# ReSpeaker_4-Mic_Array_for_Raspberry_Pi_v.net
KiCad netlist of a schematic drawn in EAGLE
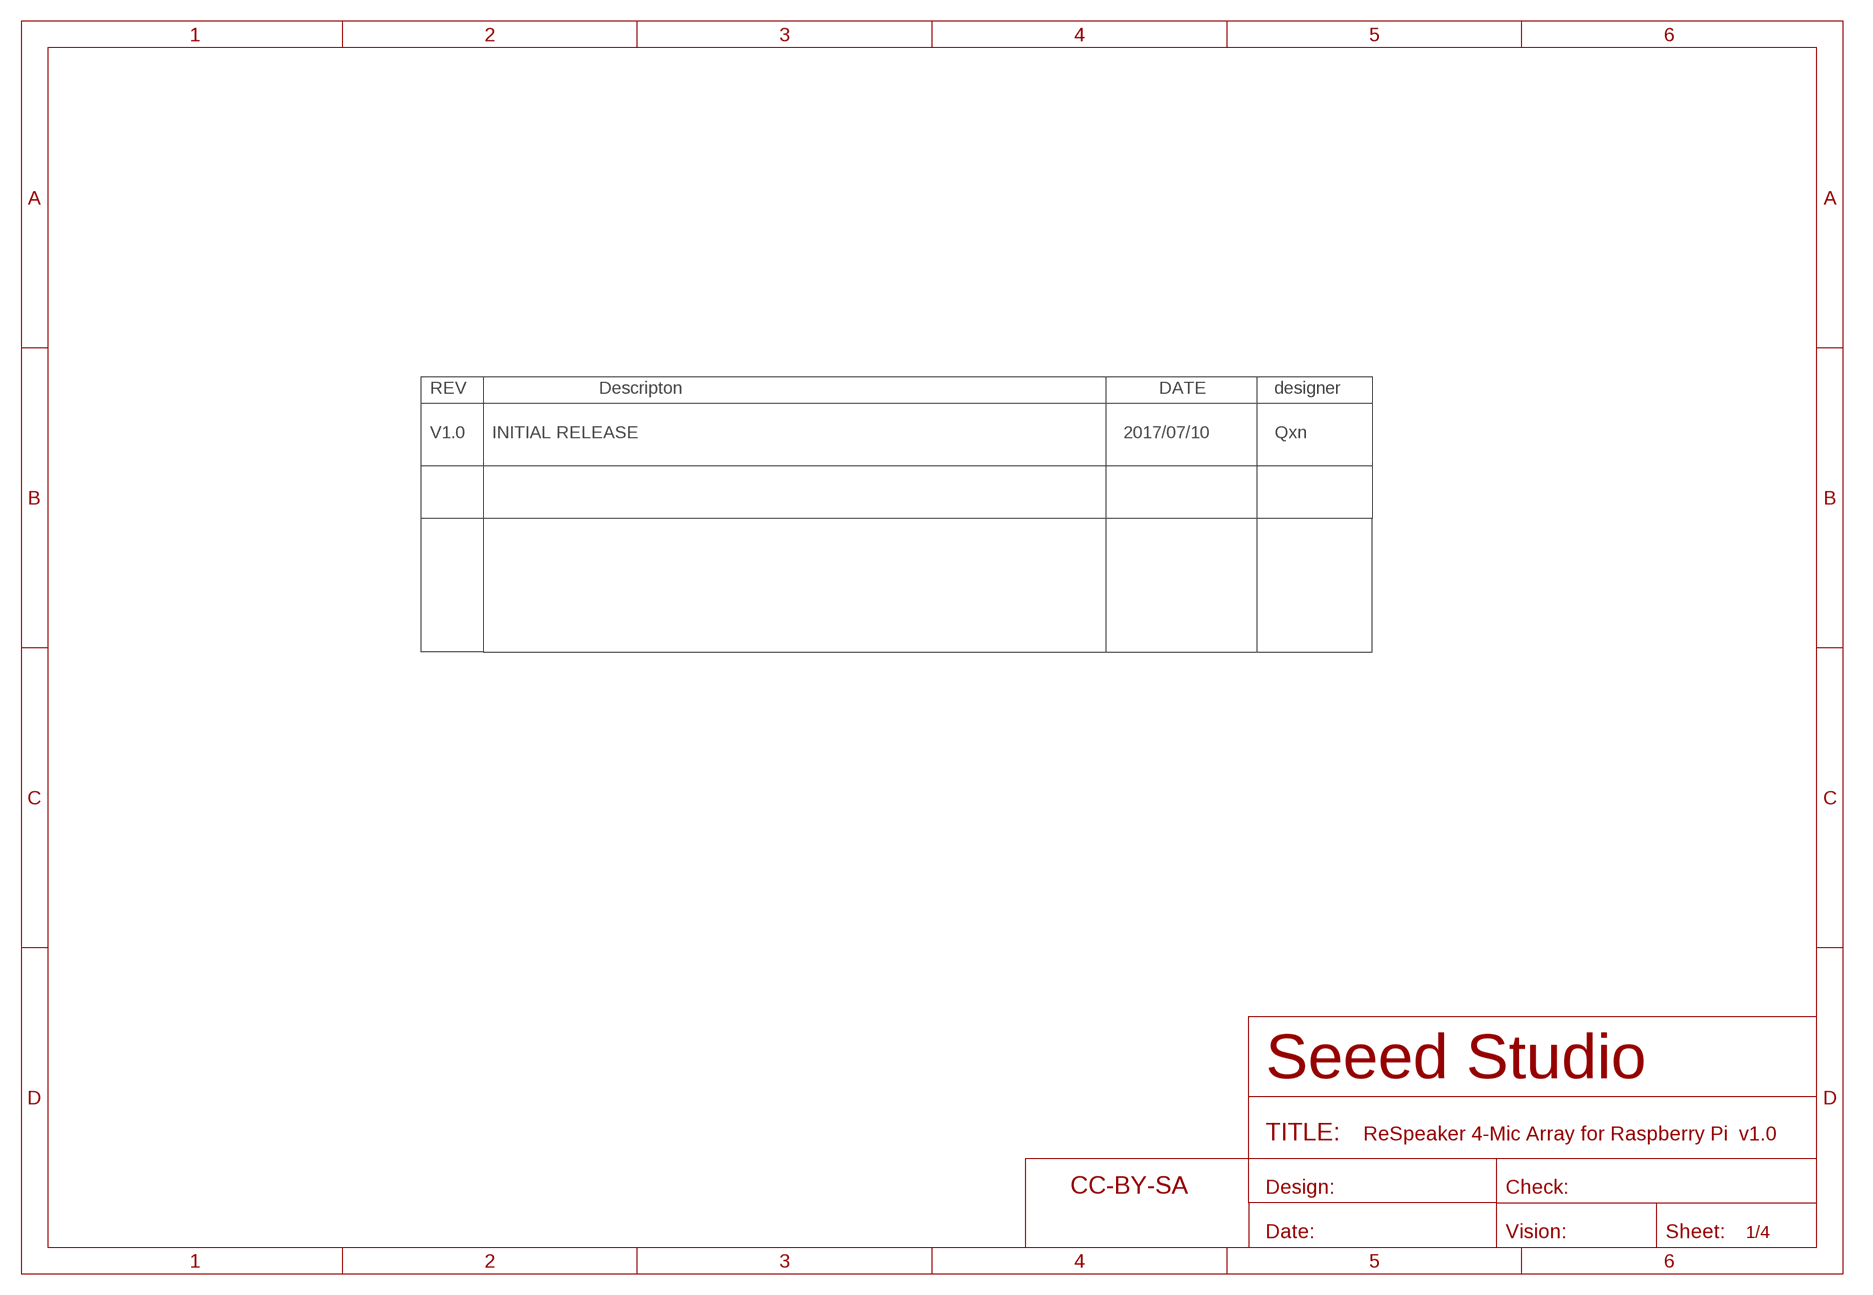
[diagram p0: schematic, sheet 1]
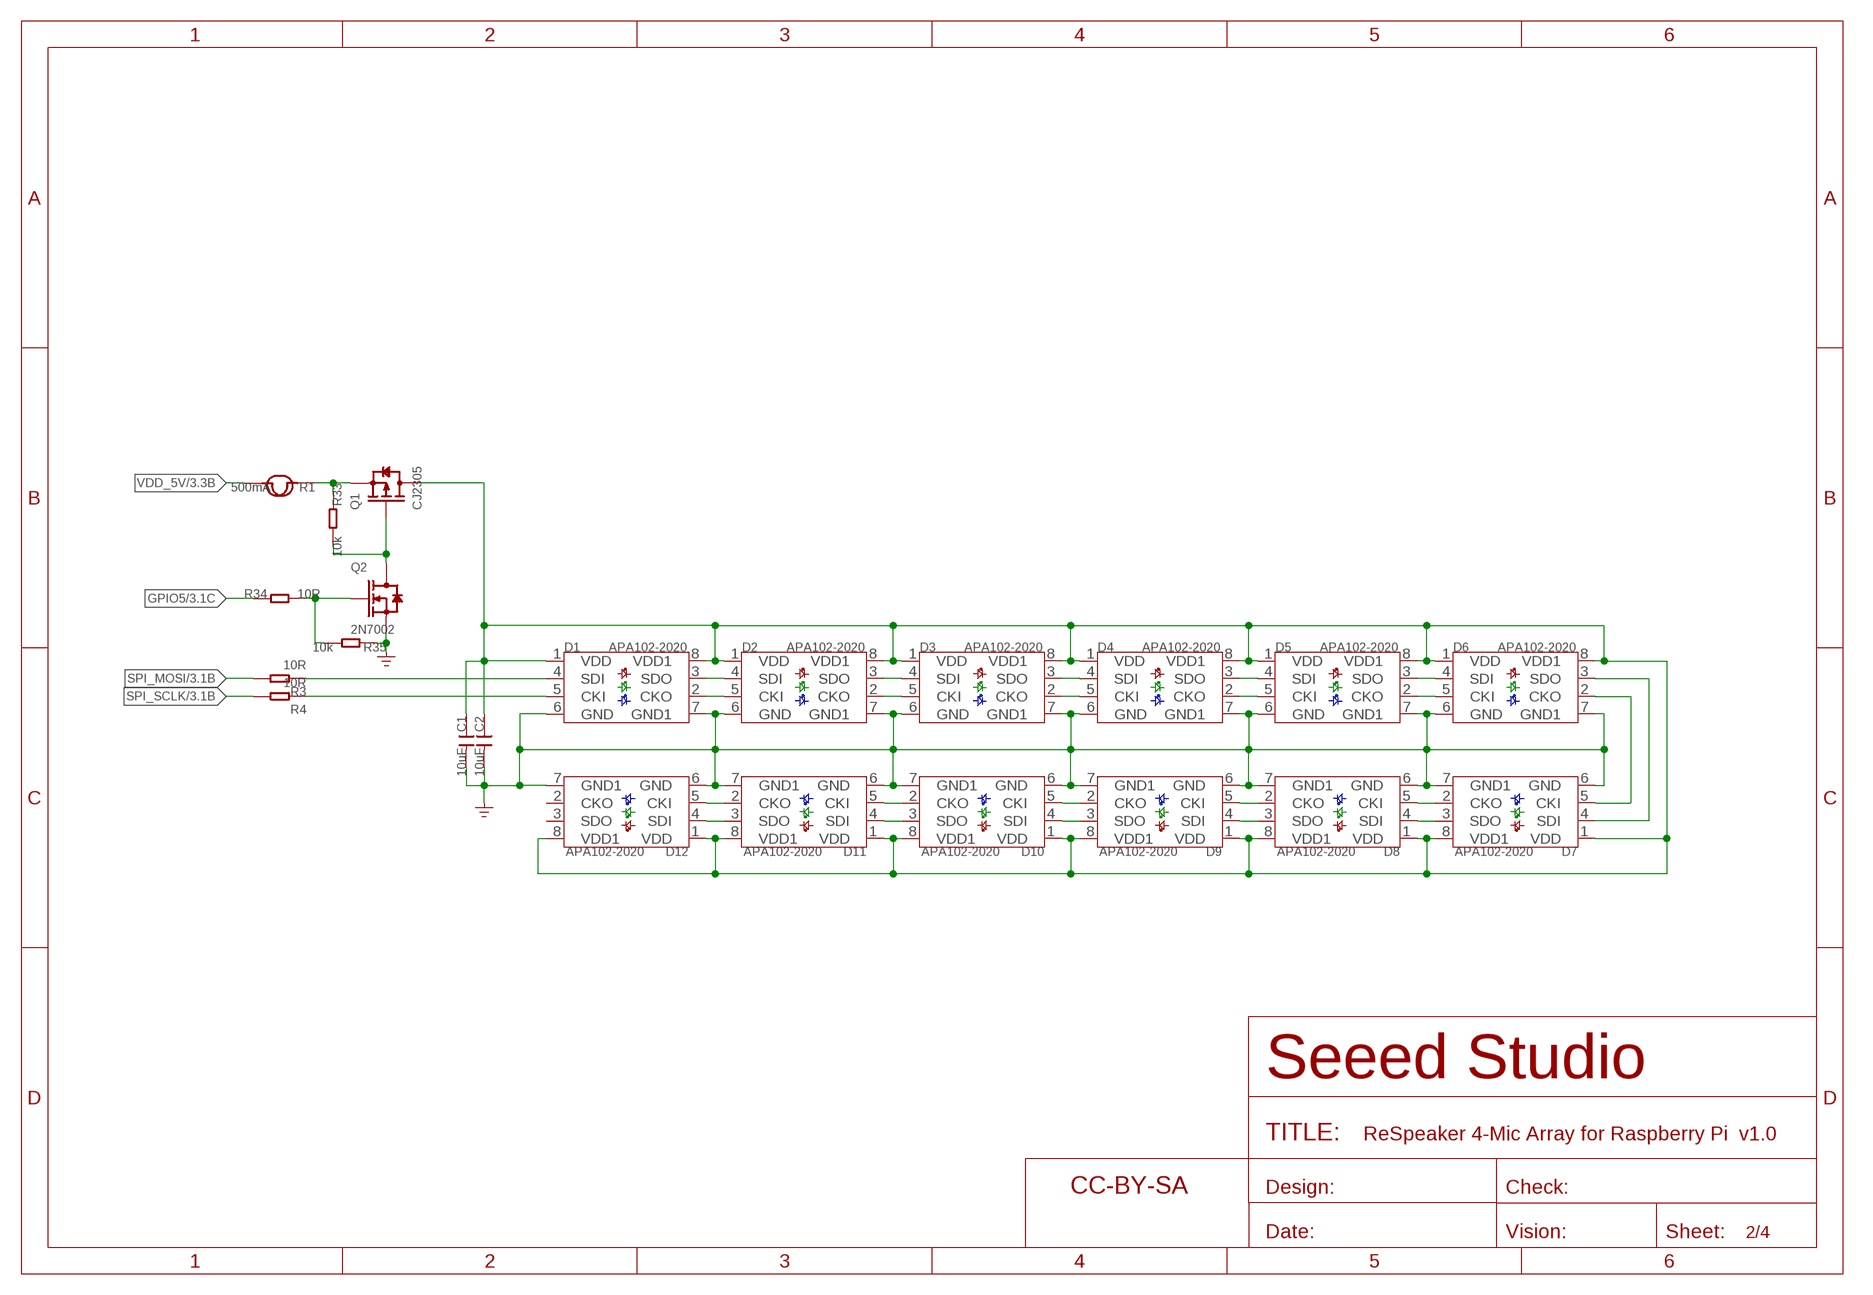
[diagram p1: schematic, sheet 2]
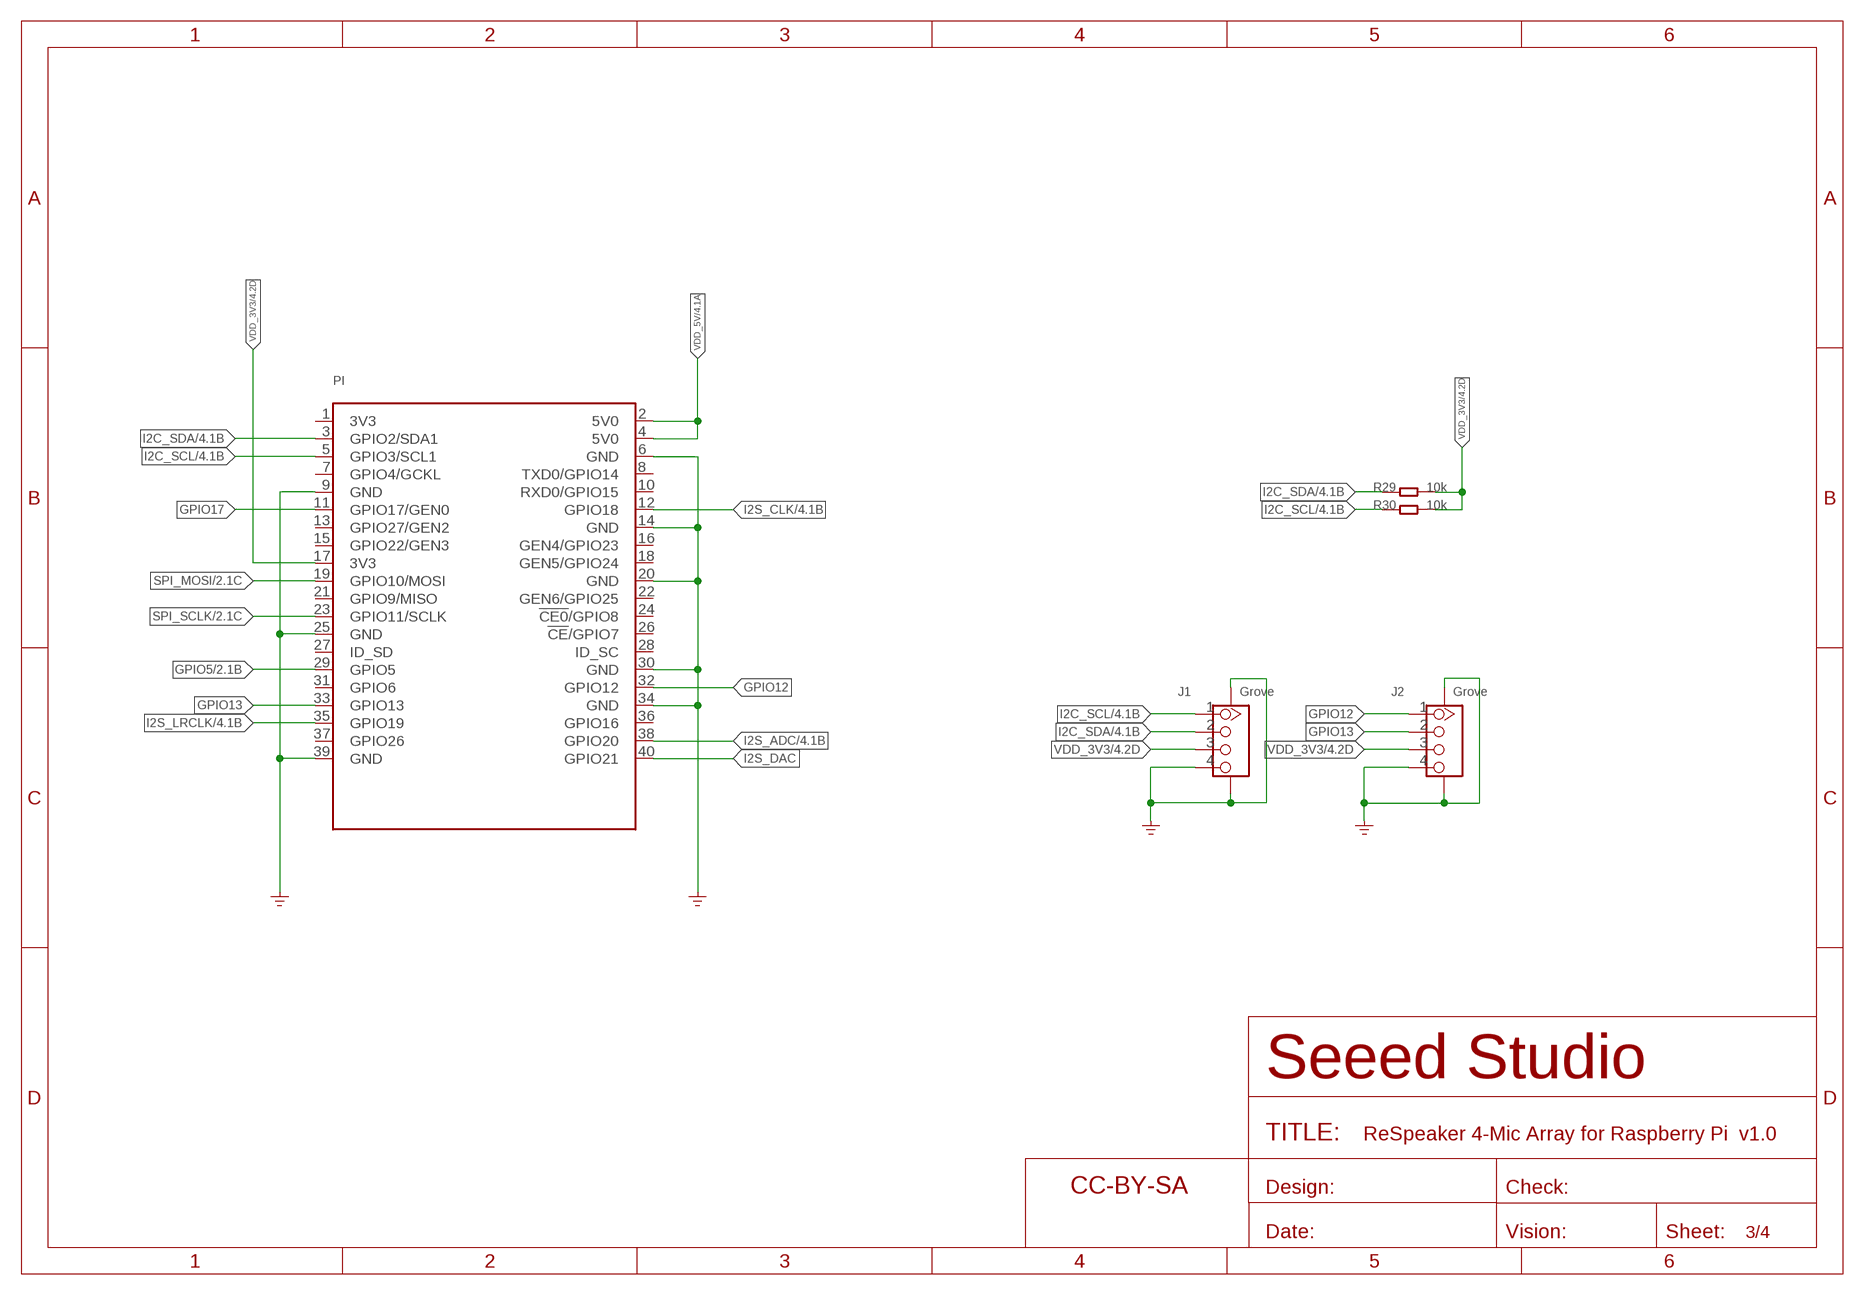
[diagram p2: schematic, sheet 3]
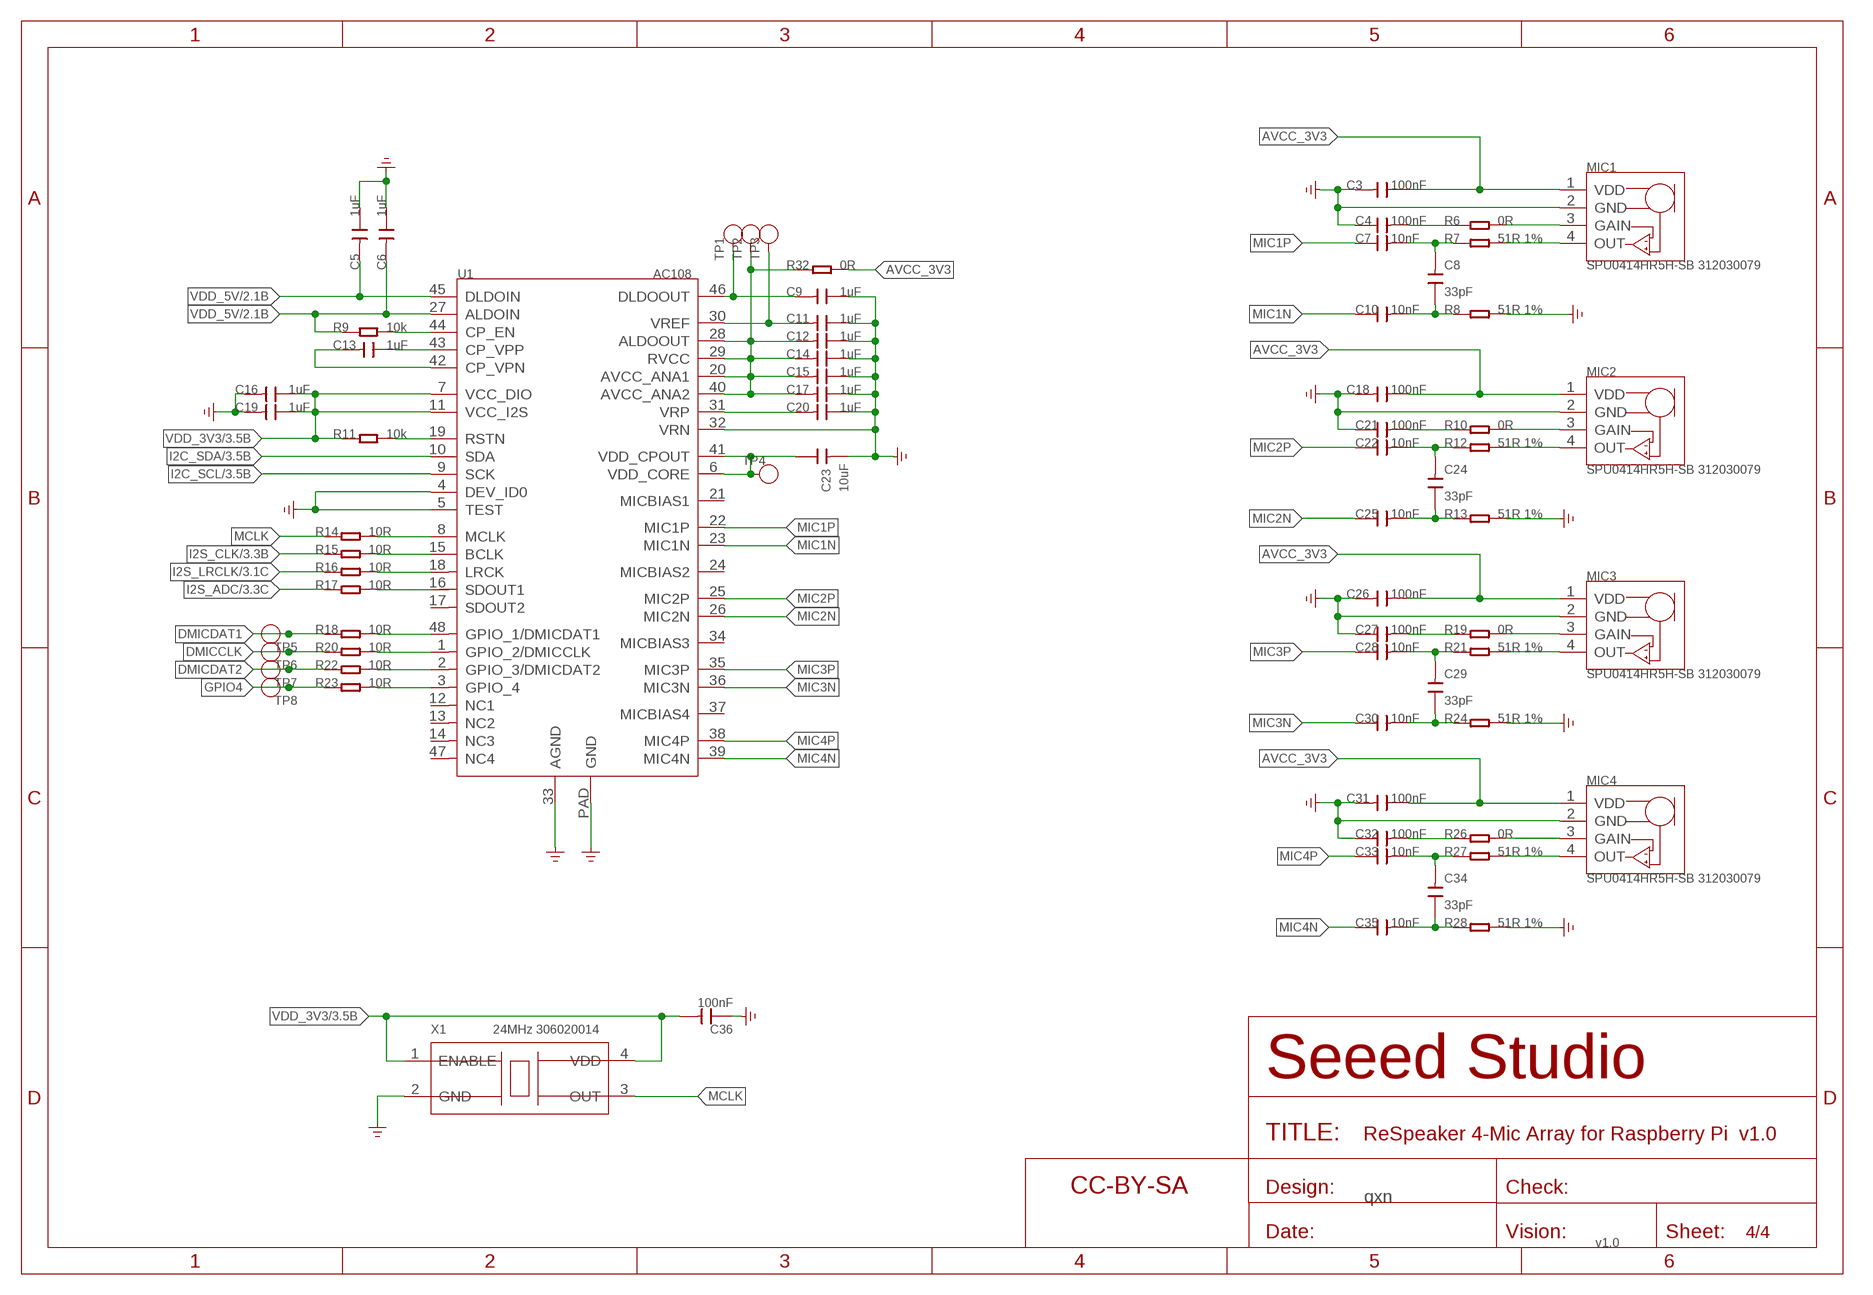
[diagram p3: schematic, sheet 4]

(export (version "E")
  (design (tool "Eeschema 10.0.6"))
  (components
    (comp (ref "FR1")
      (value "SEEEDSTUDIO-OPEN-SCH-FRAME")
      (footprint "eagle-import:SEEEDSTUDIO-PCB-FRAME")
      (libsource (lib "eagle-import") (part "SEEEDSTUDIO-OPEN-SCH-FRAME"))
    )
    (comp (ref "J1")
      (value "Grove")
      (footprint "eagle-import:HW4-SMD-2.0-90D")
      (libsource (lib "eagle-import") (part "GROVE-CONNECTOR-SMD'90D'"))
    )
    (comp (ref "J2")
      (value "Grove")
      (footprint "eagle-import:HW4-SMD-2.0-90D")
      (libsource (lib "eagle-import") (part "GROVE-CONNECTOR-SMD'90D'"))
    )
    (comp (ref "PI")
      (value "RPI-ZERO-BOTTOM")
      (footprint "eagle-import:H2X20-SMD-2.54")
      (libsource (lib "eagle-import") (part "RPI-ZERO-BOTTOM"))
    )
    (comp (ref "R29")
      (value "10k")
      (footprint "eagle-import:R0402")
      (libsource (lib "eagle-import") (part "RES-0402"))
    )
    (comp (ref "R30")
      (value "10k")
      (footprint "eagle-import:R0402")
      (libsource (lib "eagle-import") (part "RES-0402"))
    )
    (comp (ref "FR4")
      (value "SEEEDSTUDIO-OPEN-SCH-FRAME")
      (footprint "eagle-import:SEEEDSTUDIO-PCB-FRAME")
      (libsource (lib "eagle-import") (part "SEEEDSTUDIO-OPEN-SCH-FRAME"))
    )
    (comp (ref "C1")
      (value "10uF")
      (footprint "eagle-import:C0603")
      (libsource (lib "eagle-import") (part "CAP-0603"))
    )
    (comp (ref "C2")
      (value "10uF")
      (footprint "eagle-import:C0603")
      (libsource (lib "eagle-import") (part "CAP-0603"))
    )
    (comp (ref "D1")
      (value "APA102-2020")
      (footprint "eagle-import:RGB2020")
      (libsource (lib "eagle-import") (part "LED-RGB-8P-APA102-2020"))
    )
    (comp (ref "D2")
      (value "APA102-2020")
      (footprint "eagle-import:RGB2020")
      (libsource (lib "eagle-import") (part "LED-RGB-8P-APA102-2020"))
    )
    (comp (ref "D3")
      (value "APA102-2020")
      (footprint "eagle-import:RGB2020")
      (libsource (lib "eagle-import") (part "LED-RGB-8P-APA102-2020"))
    )
    (comp (ref "D4")
      (value "APA102-2020")
      (footprint "eagle-import:RGB2020")
      (libsource (lib "eagle-import") (part "LED-RGB-8P-APA102-2020"))
    )
    (comp (ref "D5")
      (value "APA102-2020")
      (footprint "eagle-import:RGB2020")
      (libsource (lib "eagle-import") (part "LED-RGB-8P-APA102-2020"))
    )
    (comp (ref "D6")
      (value "APA102-2020")
      (footprint "eagle-import:RGB2020")
      (libsource (lib "eagle-import") (part "LED-RGB-8P-APA102-2020"))
    )
    (comp (ref "D7")
      (value "APA102-2020")
      (footprint "eagle-import:RGB2020")
      (libsource (lib "eagle-import") (part "LED-RGB-8P-APA102-2020"))
    )
    (comp (ref "D8")
      (value "APA102-2020")
      (footprint "eagle-import:RGB2020")
      (libsource (lib "eagle-import") (part "LED-RGB-8P-APA102-2020"))
    )
    (comp (ref "D9")
      (value "APA102-2020")
      (footprint "eagle-import:RGB2020")
      (libsource (lib "eagle-import") (part "LED-RGB-8P-APA102-2020"))
    )
    (comp (ref "D10")
      (value "APA102-2020")
      (footprint "eagle-import:RGB2020")
      (libsource (lib "eagle-import") (part "LED-RGB-8P-APA102-2020"))
    )
    (comp (ref "D11")
      (value "APA102-2020")
      (footprint "eagle-import:RGB2020")
      (libsource (lib "eagle-import") (part "LED-RGB-8P-APA102-2020"))
    )
    (comp (ref "D12")
      (value "APA102-2020")
      (footprint "eagle-import:RGB2020")
      (libsource (lib "eagle-import") (part "LED-RGB-8P-APA102-2020"))
    )
    (comp (ref "FR3")
      (value "SEEEDSTUDIO-OPEN-SCH-FRAME")
      (footprint "eagle-import:SEEEDSTUDIO-PCB-FRAME")
      (libsource (lib "eagle-import") (part "SEEEDSTUDIO-OPEN-SCH-FRAME"))
    )
    (comp (ref "Q1")
      (value "CJ2305")
      (footprint "eagle-import:SOT-23")
      (libsource (lib "eagle-import") (part "MOSFET-P'SI2323CDS/SI2305DS{lt}BR{gt}'"))
    )
    (comp (ref "Q2")
      (value "2N7002")
      (footprint "eagle-import:SOT-23")
      (libsource (lib "eagle-import") (part "MOSFET-N'SOT23'"))
    )
    (comp (ref "R1")
      (value "500mA")
      (footprint "eagle-import:FS1206")
      (libsource (lib "eagle-import") (part "FUSE+'1206'"))
    )
    (comp (ref "R3")
      (value "10R")
      (footprint "eagle-import:R0402")
      (libsource (lib "eagle-import") (part "RES-0402"))
    )
    (comp (ref "R4")
      (value "10R")
      (footprint "eagle-import:R0402")
      (libsource (lib "eagle-import") (part "RES-0402"))
    )
    (comp (ref "R33")
      (value "10k")
      (footprint "eagle-import:R0402")
      (libsource (lib "eagle-import") (part "RES-0402"))
    )
    (comp (ref "R34")
      (value "10R")
      (footprint "eagle-import:R0402")
      (libsource (lib "eagle-import") (part "RES-0402"))
    )
    (comp (ref "R35")
      (value "10k")
      (footprint "eagle-import:R0402")
      (libsource (lib "eagle-import") (part "RES-0402"))
    )
    (comp (ref "C3")
      (value "100nF")
      (footprint "eagle-import:C0402")
      (libsource (lib "eagle-import") (part "CAP-0402"))
    )
    (comp (ref "C4")
      (value "100nF")
      (footprint "eagle-import:C0402")
      (libsource (lib "eagle-import") (part "CAP-0402"))
    )
    (comp (ref "C5")
      (value "1uF")
      (footprint "eagle-import:C0402")
      (libsource (lib "eagle-import") (part "CAP-0402"))
    )
    (comp (ref "C6")
      (value "1uF")
      (footprint "eagle-import:C0402")
      (libsource (lib "eagle-import") (part "CAP-0402"))
    )
    (comp (ref "C7")
      (value "10nF")
      (footprint "eagle-import:C0402")
      (libsource (lib "eagle-import") (part "CAP-0402"))
    )
    (comp (ref "C8")
      (value "33pF")
      (footprint "eagle-import:C0402")
      (libsource (lib "eagle-import") (part "CAP-0402"))
    )
    (comp (ref "C9")
      (value "1uF")
      (footprint "eagle-import:C0402")
      (libsource (lib "eagle-import") (part "CAP-0402"))
    )
    (comp (ref "C10")
      (value "10nF")
      (footprint "eagle-import:C0402")
      (libsource (lib "eagle-import") (part "CAP-0402"))
    )
    (comp (ref "C11")
      (value "1uF")
      (footprint "eagle-import:C0402")
      (libsource (lib "eagle-import") (part "CAP-0402"))
    )
    (comp (ref "C12")
      (value "1uF")
      (footprint "eagle-import:C0402")
      (libsource (lib "eagle-import") (part "CAP-0402"))
    )
    (comp (ref "C13")
      (value "1uF")
      (footprint "eagle-import:C0402")
      (libsource (lib "eagle-import") (part "CAP-0402"))
    )
    (comp (ref "C14")
      (value "1uF")
      (footprint "eagle-import:C0402")
      (libsource (lib "eagle-import") (part "CAP-0402"))
    )
    (comp (ref "C15")
      (value "1uF")
      (footprint "eagle-import:C0402")
      (libsource (lib "eagle-import") (part "CAP-0402"))
    )
    (comp (ref "C16")
      (value "1uF")
      (footprint "eagle-import:C0402")
      (libsource (lib "eagle-import") (part "CAP-0402"))
    )
    (comp (ref "C17")
      (value "1uF")
      (footprint "eagle-import:C0402")
      (libsource (lib "eagle-import") (part "CAP-0402"))
    )
    (comp (ref "C18")
      (value "100nF")
      (footprint "eagle-import:C0402")
      (libsource (lib "eagle-import") (part "CAP-0402"))
    )
    (comp (ref "C19")
      (value "1uF")
      (footprint "eagle-import:C0402")
      (libsource (lib "eagle-import") (part "CAP-0402"))
    )
    (comp (ref "C20")
      (value "1uF")
      (footprint "eagle-import:C0402")
      (libsource (lib "eagle-import") (part "CAP-0402"))
    )
    (comp (ref "C21")
      (value "100nF")
      (footprint "eagle-import:C0402")
      (libsource (lib "eagle-import") (part "CAP-0402"))
    )
    (comp (ref "C22")
      (value "10nF")
      (footprint "eagle-import:C0402")
      (libsource (lib "eagle-import") (part "CAP-0402"))
    )
    (comp (ref "C23")
      (value "10uF")
      (footprint "eagle-import:C0603")
      (libsource (lib "eagle-import") (part "CAP-0603"))
    )
    (comp (ref "C24")
      (value "33pF")
      (footprint "eagle-import:C0402")
      (libsource (lib "eagle-import") (part "CAP-0402"))
    )
    (comp (ref "C25")
      (value "10nF")
      (footprint "eagle-import:C0402")
      (libsource (lib "eagle-import") (part "CAP-0402"))
    )
    (comp (ref "C26")
      (value "100nF")
      (footprint "eagle-import:C0402")
      (libsource (lib "eagle-import") (part "CAP-0402"))
    )
    (comp (ref "C27")
      (value "100nF")
      (footprint "eagle-import:C0402")
      (libsource (lib "eagle-import") (part "CAP-0402"))
    )
    (comp (ref "C28")
      (value "10nF")
      (footprint "eagle-import:C0402")
      (libsource (lib "eagle-import") (part "CAP-0402"))
    )
    (comp (ref "C29")
      (value "33pF")
      (footprint "eagle-import:C0402")
      (libsource (lib "eagle-import") (part "CAP-0402"))
    )
    (comp (ref "C30")
      (value "10nF")
      (footprint "eagle-import:C0402")
      (libsource (lib "eagle-import") (part "CAP-0402"))
    )
    (comp (ref "C31")
      (value "100nF")
      (footprint "eagle-import:C0402")
      (libsource (lib "eagle-import") (part "CAP-0402"))
    )
    (comp (ref "C32")
      (value "100nF")
      (footprint "eagle-import:C0402")
      (libsource (lib "eagle-import") (part "CAP-0402"))
    )
    (comp (ref "C33")
      (value "10nF")
      (footprint "eagle-import:C0402")
      (libsource (lib "eagle-import") (part "CAP-0402"))
    )
    (comp (ref "C34")
      (value "33pF")
      (footprint "eagle-import:C0402")
      (libsource (lib "eagle-import") (part "CAP-0402"))
    )
    (comp (ref "C35")
      (value "10nF")
      (footprint "eagle-import:C0402")
      (libsource (lib "eagle-import") (part "CAP-0402"))
    )
    (comp (ref "C36")
      (value "100nF")
      (footprint "eagle-import:C0402")
      (libsource (lib "eagle-import") (part "CAP-0402"))
    )
    (comp (ref "FR2")
      (value "SEEEDSTUDIO-OPEN-SCH-FRAME")
      (footprint "eagle-import:SEEEDSTUDIO-PCB-FRAME")
      (libsource (lib "eagle-import") (part "SEEEDSTUDIO-OPEN-SCH-FRAME"))
    )
    (comp (ref "MIC1")
      (value "SPU0414HR5H-SB 312030079")
      (footprint "eagle-import:MIC4P-1.7-3.76X2.95X1.1MM")
      (libsource (lib "eagle-import") (part "MICROPHONE-SPU0414HR5H-SB"))
    )
    (comp (ref "MIC2")
      (value "SPU0414HR5H-SB 312030079")
      (footprint "eagle-import:MIC4P-1.7-3.76X2.95X1.1MM")
      (libsource (lib "eagle-import") (part "MICROPHONE-SPU0414HR5H-SB"))
    )
    (comp (ref "MIC3")
      (value "SPU0414HR5H-SB 312030079")
      (footprint "eagle-import:MIC4P-1.7-3.76X2.95X1.1MM")
      (libsource (lib "eagle-import") (part "MICROPHONE-SPU0414HR5H-SB"))
    )
    (comp (ref "MIC4")
      (value "SPU0414HR5H-SB 312030079")
      (footprint "eagle-import:MIC4P-1.7-3.76X2.95X1.1MM")
      (libsource (lib "eagle-import") (part "MICROPHONE-SPU0414HR5H-SB"))
    )
    (comp (ref "R6")
      (value "0R")
      (footprint "eagle-import:R0402")
      (libsource (lib "eagle-import") (part "RES-0402"))
    )
    (comp (ref "R7")
      (value "51R 1%")
      (footprint "eagle-import:R0402")
      (libsource (lib "eagle-import") (part "RES-0402"))
    )
    (comp (ref "R8")
      (value "51R 1%")
      (footprint "eagle-import:R0402")
      (libsource (lib "eagle-import") (part "RES-0402"))
    )
    (comp (ref "R9")
      (value "10k")
      (footprint "eagle-import:R0402")
      (libsource (lib "eagle-import") (part "RES-0402"))
    )
    (comp (ref "R10")
      (value "0R")
      (footprint "eagle-import:R0402")
      (libsource (lib "eagle-import") (part "RES-0402"))
    )
    (comp (ref "R11")
      (value "10k")
      (footprint "eagle-import:R0402")
      (libsource (lib "eagle-import") (part "RES-0402"))
    )
    (comp (ref "R12")
      (value "51R 1%")
      (footprint "eagle-import:R0402")
      (libsource (lib "eagle-import") (part "RES-0402"))
    )
    (comp (ref "R13")
      (value "51R 1%")
      (footprint "eagle-import:R0402")
      (libsource (lib "eagle-import") (part "RES-0402"))
    )
    (comp (ref "R14")
      (value "10R")
      (footprint "eagle-import:R0402")
      (libsource (lib "eagle-import") (part "RES-0402"))
    )
    (comp (ref "R15")
      (value "10R")
      (footprint "eagle-import:R0402")
      (libsource (lib "eagle-import") (part "RES-0402"))
    )
    (comp (ref "R16")
      (value "10R")
      (footprint "eagle-import:R0402")
      (libsource (lib "eagle-import") (part "RES-0402"))
    )
    (comp (ref "R17")
      (value "10R")
      (footprint "eagle-import:R0402")
      (libsource (lib "eagle-import") (part "RES-0402"))
    )
    (comp (ref "R18")
      (value "10R")
      (footprint "eagle-import:R0402")
      (libsource (lib "eagle-import") (part "RES-0402"))
    )
    (comp (ref "R19")
      (value "0R")
      (footprint "eagle-import:R0402")
      (libsource (lib "eagle-import") (part "RES-0402"))
    )
    (comp (ref "R20")
      (value "10R")
      (footprint "eagle-import:R0402")
      (libsource (lib "eagle-import") (part "RES-0402"))
    )
    (comp (ref "R21")
      (value "51R 1%")
      (footprint "eagle-import:R0402")
      (libsource (lib "eagle-import") (part "RES-0402"))
    )
    (comp (ref "R22")
      (value "10R")
      (footprint "eagle-import:R0402")
      (libsource (lib "eagle-import") (part "RES-0402"))
    )
    (comp (ref "R23")
      (value "10R")
      (footprint "eagle-import:R0402")
      (libsource (lib "eagle-import") (part "RES-0402"))
    )
    (comp (ref "R24")
      (value "51R 1%")
      (footprint "eagle-import:R0402")
      (libsource (lib "eagle-import") (part "RES-0402"))
    )
    (comp (ref "R26")
      (value "0R")
      (footprint "eagle-import:R0402")
      (libsource (lib "eagle-import") (part "RES-0402"))
    )
    (comp (ref "R27")
      (value "51R 1%")
      (footprint "eagle-import:R0402")
      (libsource (lib "eagle-import") (part "RES-0402"))
    )
    (comp (ref "R28")
      (value "51R 1%")
      (footprint "eagle-import:R0402")
      (libsource (lib "eagle-import") (part "RES-0402"))
    )
    (comp (ref "R32")
      (value "0R")
      (footprint "eagle-import:R0402")
      (libsource (lib "eagle-import") (part "RES-0402"))
    )
    (comp (ref "TP1")
      (value "TEST-POINT'4545'")
      (footprint "eagle-import:TP-D45MIL")
      (fields (field (name "PARTNO") "DNP"))
      (libsource (lib "eagle-import") (part "TEST-POINT'4545'"))
    )
    (comp (ref "TP2")
      (value "TEST-POINT'4545'")
      (footprint "eagle-import:TP-D45MIL")
      (fields (field (name "PARTNO") "DNP"))
      (libsource (lib "eagle-import") (part "TEST-POINT'4545'"))
    )
    (comp (ref "TP3")
      (value "TEST-POINT'4545'")
      (footprint "eagle-import:TP-D45MIL")
      (fields (field (name "PARTNO") "DNP"))
      (libsource (lib "eagle-import") (part "TEST-POINT'4545'"))
    )
    (comp (ref "TP4")
      (value "TEST-POINT'4545'")
      (footprint "eagle-import:TP-D45MIL")
      (fields (field (name "PARTNO") "DNP"))
      (libsource (lib "eagle-import") (part "TEST-POINT'4545'"))
    )
    (comp (ref "TP5")
      (value "TEST-POINT'4080'")
      (footprint "eagle-import:TP-80X40MIL")
      (libsource (lib "eagle-import") (part "TEST-POINT'4080'"))
    )
    (comp (ref "TP6")
      (value "TEST-POINT'4080'")
      (footprint "eagle-import:TP-80X40MIL")
      (libsource (lib "eagle-import") (part "TEST-POINT'4080'"))
    )
    (comp (ref "TP7")
      (value "TEST-POINT'4080'")
      (footprint "eagle-import:TP-80X40MIL")
      (libsource (lib "eagle-import") (part "TEST-POINT'4080'"))
    )
    (comp (ref "TP8")
      (value "TEST-POINT'4080'")
      (footprint "eagle-import:TP-80X40MIL")
      (libsource (lib "eagle-import") (part "TEST-POINT'4080'"))
    )
    (comp (ref "U1")
      (value "AC108")
      (footprint "eagle-import:QFN48G-0.4-6X6MM")
      (libsource (lib "eagle-import") (part "CONVERTER-ADC-AC108"))
    )
    (comp (ref "X1")
      (value "24MHz 306020014")
      (footprint "eagle-import:OSC4-SMD-2.5X2.0X0.8MM")
      (libsource (lib "eagle-import") (part "CRYSTAL-OSCILLATOR2.52.0"))
    )
  )
  (nets
    (net (code "1") (name "3V3") (class "Default")
      (node (ref "PI") (pin "1") (pinfunction "3V3_1") (pintype "power_in"))
    )
    (net (code "2") (name "AVCC_3V3") (class "Default")
      (node (ref "C18") (pin "1") (pinfunction "1_1") (pintype "passive"))
      (node (ref "C26") (pin "1") (pinfunction "1_1") (pintype "passive"))
      (node (ref "C3") (pin "1") (pinfunction "1_1") (pintype "passive"))
      (node (ref "C31") (pin "1") (pinfunction "1_1") (pintype "passive"))
      (node (ref "MIC1") (pin "1") (pinfunction "VDD_1") (pintype "bidirectional"))
      (node (ref "MIC2") (pin "1") (pinfunction "VDD_1") (pintype "bidirectional"))
      (node (ref "MIC3") (pin "1") (pinfunction "VDD_1") (pintype "bidirectional"))
      (node (ref "MIC4") (pin "1") (pinfunction "VDD_1") (pintype "bidirectional"))
      (node (ref "R32") (pin "1") (pinfunction "1_1") (pintype "passive"))
    )
    (net (code "3") (name "DMICCLK") (class "Default")
      (node (ref "R20") (pin "2") (pinfunction "2_2") (pintype "passive"))
      (node (ref "TP6") (pin "1") (pinfunction "T_1") (pintype "bidirectional"))
    )
    (net (code "4") (name "DMICDAT1") (class "Default")
      (node (ref "R18") (pin "2") (pinfunction "2_2") (pintype "passive"))
      (node (ref "TP5") (pin "1") (pinfunction "T_1") (pintype "bidirectional"))
    )
    (net (code "5") (name "DMICDAT2") (class "Default")
      (node (ref "R22") (pin "2") (pinfunction "2_2") (pintype "passive"))
      (node (ref "TP7") (pin "1") (pinfunction "T_1") (pintype "bidirectional"))
    )
    (net (code "6") (name "GND") (class "Default")
      (node (ref "C1") (pin "2") (pinfunction "2_2") (pintype "passive"))
      (node (ref "C11") (pin "1") (pinfunction "1_1") (pintype "passive"))
      (node (ref "C12") (pin "1") (pinfunction "1_1") (pintype "passive"))
      (node (ref "C14") (pin "1") (pinfunction "1_1") (pintype "passive"))
      (node (ref "C15") (pin "1") (pinfunction "1_1") (pintype "passive"))
      (node (ref "C16") (pin "2") (pinfunction "2_2") (pintype "passive"))
      (node (ref "C17") (pin "1") (pinfunction "1_1") (pintype "passive"))
      (node (ref "C18") (pin "2") (pinfunction "2_2") (pintype "passive"))
      (node (ref "C19") (pin "2") (pinfunction "2_2") (pintype "passive"))
      (node (ref "C2") (pin "2") (pinfunction "2_2") (pintype "passive"))
      (node (ref "C20") (pin "1") (pinfunction "1_1") (pintype "passive"))
      (node (ref "C21") (pin "1") (pinfunction "1_1") (pintype "passive"))
      (node (ref "C23") (pin "2") (pinfunction "2_2") (pintype "passive"))
      (node (ref "C26") (pin "2") (pinfunction "2_2") (pintype "passive"))
      (node (ref "C27") (pin "1") (pinfunction "1_1") (pintype "passive"))
      (node (ref "C3") (pin "2") (pinfunction "2_2") (pintype "passive"))
      (node (ref "C31") (pin "2") (pinfunction "2_2") (pintype "passive"))
      (node (ref "C32") (pin "1") (pinfunction "1_1") (pintype "passive"))
      (node (ref "C36") (pin "1") (pinfunction "1_1") (pintype "passive"))
      (node (ref "C4") (pin "1") (pinfunction "1_1") (pintype "passive"))
      (node (ref "C5") (pin "1") (pinfunction "1_1") (pintype "passive"))
      (node (ref "C6") (pin "1") (pinfunction "1_1") (pintype "passive"))
      (node (ref "C9") (pin "1") (pinfunction "1_1") (pintype "passive"))
      (node (ref "D1") (pin "6") (pinfunction "GND_6") (pintype "bidirectional"))
      (node (ref "D1") (pin "7") (pinfunction "GND1_7") (pintype "bidirectional"))
      (node (ref "D10") (pin "6") (pinfunction "GND_6") (pintype "bidirectional"))
      (node (ref "D10") (pin "7") (pinfunction "GND1_7") (pintype "bidirectional"))
      (node (ref "D11") (pin "6") (pinfunction "GND_6") (pintype "bidirectional"))
      (node (ref "D11") (pin "7") (pinfunction "GND1_7") (pintype "bidirectional"))
      (node (ref "D12") (pin "6") (pinfunction "GND_6") (pintype "bidirectional"))
      (node (ref "D12") (pin "7") (pinfunction "GND1_7") (pintype "bidirectional"))
      (node (ref "D2") (pin "6") (pinfunction "GND_6") (pintype "bidirectional"))
      (node (ref "D2") (pin "7") (pinfunction "GND1_7") (pintype "bidirectional"))
      (node (ref "D3") (pin "6") (pinfunction "GND_6") (pintype "bidirectional"))
      (node (ref "D3") (pin "7") (pinfunction "GND1_7") (pintype "bidirectional"))
      (node (ref "D4") (pin "6") (pinfunction "GND_6") (pintype "bidirectional"))
      (node (ref "D4") (pin "7") (pinfunction "GND1_7") (pintype "bidirectional"))
      (node (ref "D5") (pin "6") (pinfunction "GND_6") (pintype "bidirectional"))
      (node (ref "D5") (pin "7") (pinfunction "GND1_7") (pintype "bidirectional"))
      (node (ref "D6") (pin "6") (pinfunction "GND_6") (pintype "bidirectional"))
      (node (ref "D6") (pin "7") (pinfunction "GND1_7") (pintype "bidirectional"))
      (node (ref "D7") (pin "6") (pinfunction "GND_6") (pintype "bidirectional"))
      (node (ref "D7") (pin "7") (pinfunction "GND1_7") (pintype "bidirectional"))
      (node (ref "D8") (pin "6") (pinfunction "GND_6") (pintype "bidirectional"))
      (node (ref "D8") (pin "7") (pinfunction "GND1_7") (pintype "bidirectional"))
      (node (ref "D9") (pin "6") (pinfunction "GND_6") (pintype "bidirectional"))
      (node (ref "D9") (pin "7") (pinfunction "GND1_7") (pintype "bidirectional"))
      (node (ref "J1") (pin "4") (pinfunction "4_4") (pintype "bidirectional"))
      (node (ref "J1") (pin "SS1") (pinfunction "SS1_SS1") (pintype "bidirectional"))
      (node (ref "J1") (pin "SS2") (pinfunction "SS2_SS2") (pintype "bidirectional"))
      (node (ref "J2") (pin "4") (pinfunction "4_4") (pintype "bidirectional"))
      (node (ref "J2") (pin "SS1") (pinfunction "SS1_SS1") (pintype "bidirectional"))
      (node (ref "J2") (pin "SS2") (pinfunction "SS2_SS2") (pintype "bidirectional"))
      (node (ref "MIC1") (pin "2") (pinfunction "GND_2") (pintype "bidirectional"))
      (node (ref "MIC2") (pin "2") (pinfunction "GND_2") (pintype "bidirectional"))
      (node (ref "MIC3") (pin "2") (pinfunction "GND_2") (pintype "bidirectional"))
      (node (ref "MIC4") (pin "2") (pinfunction "GND_2") (pintype "bidirectional"))
      (node (ref "PI") (pin "14") (pinfunction "GND_14") (pintype "power_in"))
      (node (ref "PI") (pin "20") (pinfunction "GND_20") (pintype "power_in"))
      (node (ref "PI") (pin "25") (pinfunction "GND_25") (pintype "power_in"))
      (node (ref "PI") (pin "30") (pinfunction "GND_30") (pintype "power_in"))
      (node (ref "PI") (pin "34") (pinfunction "GND_34") (pintype "power_in"))
      (node (ref "PI") (pin "39") (pinfunction "GND_39") (pintype "power_in"))
      (node (ref "PI") (pin "6") (pinfunction "GND_6") (pintype "power_in"))
      (node (ref "PI") (pin "9") (pinfunction "GND_9") (pintype "power_in"))
      (node (ref "Q2") (pin "2") (pinfunction "S_2") (pintype "passive"))
      (node (ref "R13") (pin "1") (pinfunction "1_1") (pintype "passive"))
      (node (ref "R24") (pin "1") (pinfunction "1_1") (pintype "passive"))
      (node (ref "R28") (pin "1") (pinfunction "1_1") (pintype "passive"))
      (node (ref "R35") (pin "1") (pinfunction "1_1") (pintype "passive"))
      (node (ref "R8") (pin "1") (pinfunction "1_1") (pintype "passive"))
      (node (ref "U1") (pin "32") (pinfunction "VRN_32") (pintype "bidirectional"))
      (node (ref "U1") (pin "33") (pinfunction "AGND_33") (pintype "bidirectional"))
      (node (ref "U1") (pin "4") (pinfunction "DEV_ID0_4") (pintype "bidirectional"))
      (node (ref "U1") (pin "5") (pinfunction "TEST_5") (pintype "bidirectional"))
      (node (ref "U1") (pin "PAD") (pinfunction "GND_PAD") (pintype "bidirectional"))
      (node (ref "X1") (pin "2") (pinfunction "GND_2") (pintype "bidirectional"))
    )
    (net (code "7") (name "GPIO4") (class "Default")
      (node (ref "R23") (pin "2") (pinfunction "2_2") (pintype "passive"))
      (node (ref "TP8") (pin "1") (pinfunction "T_1") (pintype "bidirectional"))
    )
    (net (code "8") (name "GPIO5") (class "Default")
      (node (ref "PI") (pin "29") (pinfunction "GPIO5_29") (pintype "bidirectional"))
      (node (ref "R34") (pin "1") (pinfunction "1_1") (pintype "passive"))
    )
    (net (code "9") (name "GPIO12") (class "Default")
      (node (ref "J2") (pin "1") (pinfunction "1_1") (pintype "bidirectional"))
      (node (ref "PI") (pin "32") (pinfunction "GPIO12_32") (pintype "bidirectional"))
    )
    (net (code "10") (name "GPIO13") (class "Default")
      (node (ref "J2") (pin "2") (pinfunction "2_2") (pintype "bidirectional"))
      (node (ref "PI") (pin "33") (pinfunction "GPIO13_33") (pintype "bidirectional"))
    )
    (net (code "11") (name "GPIO17") (class "Default")
      (node (ref "PI") (pin "11") (pinfunction "GPIO17/GEN0_11") (pintype "bidirectional"))
    )
    (net (code "12") (name "I2C_SCL") (class "Default")
      (node (ref "J1") (pin "1") (pinfunction "1_1") (pintype "bidirectional"))
      (node (ref "PI") (pin "5") (pinfunction "GPIO3/SCL1_5") (pintype "bidirectional"))
      (node (ref "R30") (pin "1") (pinfunction "1_1") (pintype "passive"))
      (node (ref "U1") (pin "9") (pinfunction "SCK_9") (pintype "bidirectional"))
    )
    (net (code "13") (name "I2C_SDA") (class "Default")
      (node (ref "J1") (pin "2") (pinfunction "2_2") (pintype "bidirectional"))
      (node (ref "PI") (pin "3") (pinfunction "GPIO2/SDA1_3") (pintype "bidirectional"))
      (node (ref "R29") (pin "1") (pinfunction "1_1") (pintype "passive"))
      (node (ref "U1") (pin "10") (pinfunction "SDA_10") (pintype "bidirectional"))
    )
    (net (code "14") (name "I2S_ADC") (class "Default")
      (node (ref "PI") (pin "38") (pinfunction "GPIO20_38") (pintype "bidirectional"))
      (node (ref "R17") (pin "2") (pinfunction "2_2") (pintype "passive"))
    )
    (net (code "15") (name "I2S_CLK") (class "Default")
      (node (ref "PI") (pin "12") (pinfunction "GPIO18_12") (pintype "bidirectional"))
      (node (ref "R15") (pin "2") (pinfunction "2_2") (pintype "passive"))
    )
    (net (code "16") (name "I2S_DAC") (class "Default")
      (node (ref "PI") (pin "40") (pinfunction "GPIO21_40") (pintype "bidirectional"))
    )
    (net (code "17") (name "I2S_LRCLK") (class "Default")
      (node (ref "PI") (pin "35") (pinfunction "GPIO19_35") (pintype "bidirectional"))
      (node (ref "R16") (pin "2") (pinfunction "2_2") (pintype "passive"))
    )
    (net (code "18") (name "MCLK") (class "Default")
      (node (ref "R14") (pin "2") (pinfunction "2_2") (pintype "passive"))
      (node (ref "X1") (pin "3") (pinfunction "OUT_3") (pintype "bidirectional"))
    )
    (net (code "19") (name "MIC1N") (class "Default")
      (node (ref "C10") (pin "1") (pinfunction "1_1") (pintype "passive"))
      (node (ref "U1") (pin "23") (pinfunction "MIC1N_23") (pintype "bidirectional"))
    )
    (net (code "20") (name "MIC1P") (class "Default")
      (node (ref "C7") (pin "1") (pinfunction "1_1") (pintype "passive"))
      (node (ref "U1") (pin "22") (pinfunction "MIC1P_22") (pintype "bidirectional"))
    )
    (net (code "21") (name "MIC2N") (class "Default")
      (node (ref "C25") (pin "1") (pinfunction "1_1") (pintype "passive"))
      (node (ref "U1") (pin "26") (pinfunction "MIC2N_26") (pintype "bidirectional"))
    )
    (net (code "22") (name "MIC2P") (class "Default")
      (node (ref "C22") (pin "1") (pinfunction "1_1") (pintype "passive"))
      (node (ref "U1") (pin "25") (pinfunction "MIC2P_25") (pintype "bidirectional"))
    )
    (net (code "23") (name "MIC3N") (class "Default")
      (node (ref "C30") (pin "1") (pinfunction "1_1") (pintype "passive"))
      (node (ref "U1") (pin "36") (pinfunction "MIC3N_36") (pintype "bidirectional"))
    )
    (net (code "24") (name "MIC3P") (class "Default")
      (node (ref "C28") (pin "1") (pinfunction "1_1") (pintype "passive"))
      (node (ref "U1") (pin "35") (pinfunction "MIC3P_35") (pintype "bidirectional"))
    )
    (net (code "25") (name "MIC4N") (class "Default")
      (node (ref "C35") (pin "1") (pinfunction "1_1") (pintype "passive"))
      (node (ref "U1") (pin "39") (pinfunction "MIC4N_39") (pintype "bidirectional"))
    )
    (net (code "26") (name "MIC4P") (class "Default")
      (node (ref "C33") (pin "1") (pinfunction "1_1") (pintype "passive"))
      (node (ref "U1") (pin "38") (pinfunction "MIC4P_38") (pintype "bidirectional"))
    )
    (net (code "27") (name "Net-(C4-Pad2)") (class "Default")
      (node (ref "C4") (pin "2") (pinfunction "2_2") (pintype "passive"))
      (node (ref "R6") (pin "2") (pinfunction "2_2") (pintype "passive"))
    )
    (net (code "28") (name "Net-(C7-Pad2)") (class "Default")
      (node (ref "C7") (pin "2") (pinfunction "2_2") (pintype "passive"))
      (node (ref "C8") (pin "2") (pinfunction "2_2") (pintype "passive"))
      (node (ref "R7") (pin "2") (pinfunction "2_2") (pintype "passive"))
    )
    (net (code "29") (name "Net-(C10-Pad2)") (class "Default")
      (node (ref "C10") (pin "2") (pinfunction "2_2") (pintype "passive"))
      (node (ref "C8") (pin "1") (pinfunction "1_1") (pintype "passive"))
      (node (ref "R8") (pin "2") (pinfunction "2_2") (pintype "passive"))
    )
    (net (code "30") (name "Net-(C21-Pad2)") (class "Default")
      (node (ref "C21") (pin "2") (pinfunction "2_2") (pintype "passive"))
      (node (ref "R10") (pin "2") (pinfunction "2_2") (pintype "passive"))
    )
    (net (code "31") (name "Net-(C22-Pad2)") (class "Default")
      (node (ref "C22") (pin "2") (pinfunction "2_2") (pintype "passive"))
      (node (ref "C24") (pin "2") (pinfunction "2_2") (pintype "passive"))
      (node (ref "R12") (pin "2") (pinfunction "2_2") (pintype "passive"))
    )
    (net (code "32") (name "Net-(C24-Pad1)") (class "Default")
      (node (ref "C24") (pin "1") (pinfunction "1_1") (pintype "passive"))
      (node (ref "C25") (pin "2") (pinfunction "2_2") (pintype "passive"))
      (node (ref "R13") (pin "2") (pinfunction "2_2") (pintype "passive"))
    )
    (net (code "33") (name "Net-(C27-Pad2)") (class "Default")
      (node (ref "C27") (pin "2") (pinfunction "2_2") (pintype "passive"))
      (node (ref "R19") (pin "2") (pinfunction "2_2") (pintype "passive"))
    )
    (net (code "34") (name "Net-(C28-Pad2)") (class "Default")
      (node (ref "C28") (pin "2") (pinfunction "2_2") (pintype "passive"))
      (node (ref "C29") (pin "2") (pinfunction "2_2") (pintype "passive"))
      (node (ref "R21") (pin "2") (pinfunction "2_2") (pintype "passive"))
    )
    (net (code "35") (name "Net-(C29-Pad1)") (class "Default")
      (node (ref "C29") (pin "1") (pinfunction "1_1") (pintype "passive"))
      (node (ref "C30") (pin "2") (pinfunction "2_2") (pintype "passive"))
      (node (ref "R24") (pin "2") (pinfunction "2_2") (pintype "passive"))
    )
    (net (code "36") (name "Net-(C32-Pad2)") (class "Default")
      (node (ref "C32") (pin "2") (pinfunction "2_2") (pintype "passive"))
      (node (ref "R26") (pin "2") (pinfunction "2_2") (pintype "passive"))
    )
    (net (code "37") (name "Net-(C33-Pad2)") (class "Default")
      (node (ref "C33") (pin "2") (pinfunction "2_2") (pintype "passive"))
      (node (ref "C34") (pin "2") (pinfunction "2_2") (pintype "passive"))
      (node (ref "R27") (pin "2") (pinfunction "2_2") (pintype "passive"))
    )
    (net (code "38") (name "Net-(C34-Pad1)") (class "Default")
      (node (ref "C34") (pin "1") (pinfunction "1_1") (pintype "passive"))
      (node (ref "C35") (pin "2") (pinfunction "2_2") (pintype "passive"))
      (node (ref "R28") (pin "2") (pinfunction "2_2") (pintype "passive"))
    )
    (net (code "39") (name "Net-(D1-CKI)") (class "Default")
      (node (ref "D1") (pin "5") (pinfunction "CKI_5") (pintype "bidirectional"))
      (node (ref "R4") (pin "1") (pinfunction "1_1") (pintype "passive"))
    )
    (net (code "40") (name "Net-(D1-CKO)") (class "Default")
      (node (ref "D1") (pin "2") (pinfunction "CKO_2") (pintype "bidirectional"))
      (node (ref "D2") (pin "5") (pinfunction "CKI_5") (pintype "bidirectional"))
    )
    (net (code "41") (name "Net-(D1-SDI)") (class "Default")
      (node (ref "D1") (pin "4") (pinfunction "SDI_4") (pintype "bidirectional"))
      (node (ref "R3") (pin "1") (pinfunction "1_1") (pintype "passive"))
    )
    (net (code "42") (name "Net-(D1-SDO)") (class "Default")
      (node (ref "D1") (pin "3") (pinfunction "SDO_3") (pintype "bidirectional"))
      (node (ref "D2") (pin "4") (pinfunction "SDI_4") (pintype "bidirectional"))
    )
    (net (code "43") (name "Net-(D1-VDD)") (class "Default")
      (node (ref "C1") (pin "1") (pinfunction "1_1") (pintype "passive"))
      (node (ref "C2") (pin "1") (pinfunction "1_1") (pintype "passive"))
      (node (ref "D1") (pin "1") (pinfunction "VDD_1") (pintype "bidirectional"))
      (node (ref "D1") (pin "8") (pinfunction "VDD1_8") (pintype "bidirectional"))
      (node (ref "D10") (pin "1") (pinfunction "VDD_1") (pintype "bidirectional"))
      (node (ref "D10") (pin "8") (pinfunction "VDD1_8") (pintype "bidirectional"))
      (node (ref "D11") (pin "1") (pinfunction "VDD_1") (pintype "bidirectional"))
      (node (ref "D11") (pin "8") (pinfunction "VDD1_8") (pintype "bidirectional"))
      (node (ref "D12") (pin "1") (pinfunction "VDD_1") (pintype "bidirectional"))
      (node (ref "D12") (pin "8") (pinfunction "VDD1_8") (pintype "bidirectional"))
      (node (ref "D2") (pin "1") (pinfunction "VDD_1") (pintype "bidirectional"))
      (node (ref "D2") (pin "8") (pinfunction "VDD1_8") (pintype "bidirectional"))
      (node (ref "D3") (pin "1") (pinfunction "VDD_1") (pintype "bidirectional"))
      (node (ref "D3") (pin "8") (pinfunction "VDD1_8") (pintype "bidirectional"))
      (node (ref "D4") (pin "1") (pinfunction "VDD_1") (pintype "bidirectional"))
      (node (ref "D4") (pin "8") (pinfunction "VDD1_8") (pintype "bidirectional"))
      (node (ref "D5") (pin "1") (pinfunction "VDD_1") (pintype "bidirectional"))
      (node (ref "D5") (pin "8") (pinfunction "VDD1_8") (pintype "bidirectional"))
      (node (ref "D6") (pin "1") (pinfunction "VDD_1") (pintype "bidirectional"))
      (node (ref "D6") (pin "8") (pinfunction "VDD1_8") (pintype "bidirectional"))
      (node (ref "D7") (pin "1") (pinfunction "VDD_1") (pintype "bidirectional"))
      (node (ref "D7") (pin "8") (pinfunction "VDD1_8") (pintype "bidirectional"))
      (node (ref "D8") (pin "1") (pinfunction "VDD_1") (pintype "bidirectional"))
      (node (ref "D8") (pin "8") (pinfunction "VDD1_8") (pintype "bidirectional"))
      (node (ref "D9") (pin "1") (pinfunction "VDD_1") (pintype "bidirectional"))
      (node (ref "D9") (pin "8") (pinfunction "VDD1_8") (pintype "bidirectional"))
      (node (ref "Q1") (pin "3") (pinfunction "D_3") (pintype "passive"))
    )
    (net (code "44") (name "Net-(D2-CKO)") (class "Default")
      (node (ref "D2") (pin "2") (pinfunction "CKO_2") (pintype "bidirectional"))
      (node (ref "D3") (pin "5") (pinfunction "CKI_5") (pintype "bidirectional"))
    )
    (net (code "45") (name "Net-(D2-SDO)") (class "Default")
      (node (ref "D2") (pin "3") (pinfunction "SDO_3") (pintype "bidirectional"))
      (node (ref "D3") (pin "4") (pinfunction "SDI_4") (pintype "bidirectional"))
    )
    (net (code "46") (name "Net-(D3-CKO)") (class "Default")
      (node (ref "D3") (pin "2") (pinfunction "CKO_2") (pintype "bidirectional"))
      (node (ref "D4") (pin "5") (pinfunction "CKI_5") (pintype "bidirectional"))
    )
    (net (code "47") (name "Net-(D3-SDO)") (class "Default")
      (node (ref "D3") (pin "3") (pinfunction "SDO_3") (pintype "bidirectional"))
      (node (ref "D4") (pin "4") (pinfunction "SDI_4") (pintype "bidirectional"))
    )
    (net (code "48") (name "Net-(D4-CKO)") (class "Default")
      (node (ref "D4") (pin "2") (pinfunction "CKO_2") (pintype "bidirectional"))
      (node (ref "D5") (pin "5") (pinfunction "CKI_5") (pintype "bidirectional"))
    )
    (net (code "49") (name "Net-(D4-SDO)") (class "Default")
      (node (ref "D4") (pin "3") (pinfunction "SDO_3") (pintype "bidirectional"))
      (node (ref "D5") (pin "4") (pinfunction "SDI_4") (pintype "bidirectional"))
    )
    (net (code "50") (name "Net-(D5-CKO)") (class "Default")
      (node (ref "D5") (pin "2") (pinfunction "CKO_2") (pintype "bidirectional"))
      (node (ref "D6") (pin "5") (pinfunction "CKI_5") (pintype "bidirectional"))
    )
    (net (code "51") (name "Net-(D5-SDO)") (class "Default")
      (node (ref "D5") (pin "3") (pinfunction "SDO_3") (pintype "bidirectional"))
      (node (ref "D6") (pin "4") (pinfunction "SDI_4") (pintype "bidirectional"))
    )
    (net (code "52") (name "Net-(D6-CKO)") (class "Default")
      (node (ref "D6") (pin "2") (pinfunction "CKO_2") (pintype "bidirectional"))
      (node (ref "D7") (pin "5") (pinfunction "CKI_5") (pintype "bidirectional"))
    )
    (net (code "53") (name "Net-(D6-SDO)") (class "Default")
      (node (ref "D6") (pin "3") (pinfunction "SDO_3") (pintype "bidirectional"))
      (node (ref "D7") (pin "4") (pinfunction "SDI_4") (pintype "bidirectional"))
    )
    (net (code "54") (name "Net-(D7-CKO)") (class "Default")
      (node (ref "D7") (pin "2") (pinfunction "CKO_2") (pintype "bidirectional"))
      (node (ref "D8") (pin "5") (pinfunction "CKI_5") (pintype "bidirectional"))
    )
    (net (code "55") (name "Net-(D7-SDO)") (class "Default")
      (node (ref "D7") (pin "3") (pinfunction "SDO_3") (pintype "bidirectional"))
      (node (ref "D8") (pin "4") (pinfunction "SDI_4") (pintype "bidirectional"))
    )
    (net (code "56") (name "Net-(D8-CKO)") (class "Default")
      (node (ref "D8") (pin "2") (pinfunction "CKO_2") (pintype "bidirectional"))
      (node (ref "D9") (pin "5") (pinfunction "CKI_5") (pintype "bidirectional"))
    )
    (net (code "57") (name "Net-(D8-SDO)") (class "Default")
      (node (ref "D8") (pin "3") (pinfunction "SDO_3") (pintype "bidirectional"))
      (node (ref "D9") (pin "4") (pinfunction "SDI_4") (pintype "bidirectional"))
    )
    (net (code "58") (name "Net-(D10-CKI)") (class "Default")
      (node (ref "D10") (pin "5") (pinfunction "CKI_5") (pintype "bidirectional"))
      (node (ref "D9") (pin "2") (pinfunction "CKO_2") (pintype "bidirectional"))
    )
    (net (code "59") (name "Net-(D10-CKO)") (class "Default")
      (node (ref "D10") (pin "2") (pinfunction "CKO_2") (pintype "bidirectional"))
      (node (ref "D11") (pin "5") (pinfunction "CKI_5") (pintype "bidirectional"))
    )
    (net (code "60") (name "Net-(D10-SDI)") (class "Default")
      (node (ref "D10") (pin "4") (pinfunction "SDI_4") (pintype "bidirectional"))
      (node (ref "D9") (pin "3") (pinfunction "SDO_3") (pintype "bidirectional"))
    )
    (net (code "61") (name "Net-(D10-SDO)") (class "Default")
      (node (ref "D10") (pin "3") (pinfunction "SDO_3") (pintype "bidirectional"))
      (node (ref "D11") (pin "4") (pinfunction "SDI_4") (pintype "bidirectional"))
    )
    (net (code "62") (name "Net-(D11-CKO)") (class "Default")
      (node (ref "D11") (pin "2") (pinfunction "CKO_2") (pintype "bidirectional"))
      (node (ref "D12") (pin "5") (pinfunction "CKI_5") (pintype "bidirectional"))
    )
    (net (code "63") (name "Net-(D11-SDO)") (class "Default")
      (node (ref "D11") (pin "3") (pinfunction "SDO_3") (pintype "bidirectional"))
      (node (ref "D12") (pin "4") (pinfunction "SDI_4") (pintype "bidirectional"))
    )
    (net (code "64") (name "Net-(MIC1-GAIN)") (class "Default")
      (node (ref "MIC1") (pin "3") (pinfunction "GAIN_3") (pintype "bidirectional"))
      (node (ref "R6") (pin "1") (pinfunction "1_1") (pintype "passive"))
    )
    (net (code "65") (name "Net-(MIC1-OUT)") (class "Default")
      (node (ref "MIC1") (pin "4") (pinfunction "OUT_4") (pintype "bidirectional"))
      (node (ref "R7") (pin "1") (pinfunction "1_1") (pintype "passive"))
    )
    (net (code "66") (name "Net-(MIC2-GAIN)") (class "Default")
      (node (ref "MIC2") (pin "3") (pinfunction "GAIN_3") (pintype "bidirectional"))
      (node (ref "R10") (pin "1") (pinfunction "1_1") (pintype "passive"))
    )
    (net (code "67") (name "Net-(MIC2-OUT)") (class "Default")
      (node (ref "MIC2") (pin "4") (pinfunction "OUT_4") (pintype "bidirectional"))
      (node (ref "R12") (pin "1") (pinfunction "1_1") (pintype "passive"))
    )
    (net (code "68") (name "Net-(MIC3-GAIN)") (class "Default")
      (node (ref "MIC3") (pin "3") (pinfunction "GAIN_3") (pintype "bidirectional"))
      (node (ref "R19") (pin "1") (pinfunction "1_1") (pintype "passive"))
    )
    (net (code "69") (name "Net-(MIC3-OUT)") (class "Default")
      (node (ref "MIC3") (pin "4") (pinfunction "OUT_4") (pintype "bidirectional"))
      (node (ref "R21") (pin "1") (pinfunction "1_1") (pintype "passive"))
    )
    (net (code "70") (name "Net-(MIC4-GAIN)") (class "Default")
      (node (ref "MIC4") (pin "3") (pinfunction "GAIN_3") (pintype "bidirectional"))
      (node (ref "R26") (pin "1") (pinfunction "1_1") (pintype "passive"))
    )
    (net (code "71") (name "Net-(MIC4-OUT)") (class "Default")
      (node (ref "MIC4") (pin "4") (pinfunction "OUT_4") (pintype "bidirectional"))
      (node (ref "R27") (pin "1") (pinfunction "1_1") (pintype "passive"))
    )
    (net (code "72") (name "Net-(Q1-G)") (class "Default")
      (node (ref "Q1") (pin "1") (pinfunction "G_1") (pintype "passive"))
      (node (ref "Q2") (pin "3") (pinfunction "D_3") (pintype "passive"))
      (node (ref "R33") (pin "2") (pinfunction "2_2") (pintype "passive"))
    )
    (net (code "73") (name "Net-(Q1-S)") (class "Default")
      (node (ref "Q1") (pin "2") (pinfunction "S_2") (pintype "passive"))
      (node (ref "R1") (pin "1") (pinfunction "1_1") (pintype "bidirectional"))
      (node (ref "R33") (pin "1") (pinfunction "1_1") (pintype "passive"))
    )
    (net (code "74") (name "Net-(Q2-G)") (class "Default")
      (node (ref "Q2") (pin "1") (pinfunction "G_1") (pintype "passive"))
      (node (ref "R34") (pin "2") (pinfunction "2_2") (pintype "passive"))
      (node (ref "R35") (pin "2") (pinfunction "2_2") (pintype "passive"))
    )
    (net (code "75") (name "Net-(U1-ALDOOUT)") (class "Default")
      (node (ref "C12") (pin "2") (pinfunction "2_2") (pintype "passive"))
      (node (ref "C14") (pin "2") (pinfunction "2_2") (pintype "passive"))
      (node (ref "C15") (pin "2") (pinfunction "2_2") (pintype "passive"))
      (node (ref "C17") (pin "2") (pinfunction "2_2") (pintype "passive"))
      (node (ref "R32") (pin "2") (pinfunction "2_2") (pintype "passive"))
      (node (ref "TP2") (pin "T") (pinfunction "T_T") (pintype "bidirectional"))
      (node (ref "U1") (pin "20") (pinfunction "AVCC_ANA1_20") (pintype "bidirectional"))
      (node (ref "U1") (pin "28") (pinfunction "ALDOOUT_28") (pintype "bidirectional"))
      (node (ref "U1") (pin "29") (pinfunction "RVCC_29") (pintype "bidirectional"))
      (node (ref "U1") (pin "40") (pinfunction "AVCC_ANA2_40") (pintype "bidirectional"))
    )
    (net (code "76") (name "Net-(U1-BCLK)") (class "Default")
      (node (ref "R15") (pin "1") (pinfunction "1_1") (pintype "passive"))
      (node (ref "U1") (pin "15") (pinfunction "BCLK_15") (pintype "bidirectional"))
    )
    (net (code "77") (name "Net-(U1-CP_EN)") (class "Default")
      (node (ref "R9") (pin "2") (pinfunction "2_2") (pintype "passive"))
      (node (ref "U1") (pin "44") (pinfunction "CP_EN_44") (pintype "bidirectional"))
    )
    (net (code "78") (name "Net-(U1-CP_VPN)") (class "Default")
      (node (ref "C13") (pin "2") (pinfunction "2_2") (pintype "passive"))
      (node (ref "U1") (pin "42") (pinfunction "CP_VPN_42") (pintype "bidirectional"))
    )
    (net (code "79") (name "Net-(U1-CP_VPP)") (class "Default")
      (node (ref "C13") (pin "1") (pinfunction "1_1") (pintype "passive"))
      (node (ref "U1") (pin "43") (pinfunction "CP_VPP_43") (pintype "bidirectional"))
    )
    (net (code "80") (name "Net-(U1-DLDOOUT)") (class "Default")
      (node (ref "C9") (pin "2") (pinfunction "2_2") (pintype "passive"))
      (node (ref "TP1") (pin "T") (pinfunction "T_T") (pintype "bidirectional"))
      (node (ref "U1") (pin "46") (pinfunction "DLDOOUT_46") (pintype "bidirectional"))
    )
    (net (code "81") (name "Net-(U1-GPIO_1{slash}DMICDAT1)") (class "Default")
      (node (ref "R18") (pin "1") (pinfunction "1_1") (pintype "passive"))
      (node (ref "U1") (pin "48") (pinfunction "GPIO_1/DMICDAT1_48") (pintype "bidirectional"))
    )
    (net (code "82") (name "Net-(U1-GPIO_2{slash}DMICCLK)") (class "Default")
      (node (ref "R20") (pin "1") (pinfunction "1_1") (pintype "passive"))
      (node (ref "U1") (pin "1") (pinfunction "GPIO_2/DMICCLK_1") (pintype "bidirectional"))
    )
    (net (code "83") (name "Net-(U1-GPIO_3{slash}DMICDAT2)") (class "Default")
      (node (ref "R22") (pin "1") (pinfunction "1_1") (pintype "passive"))
      (node (ref "U1") (pin "2") (pinfunction "GPIO_3/DMICDAT2_2") (pintype "bidirectional"))
    )
    (net (code "84") (name "Net-(U1-GPIO_4)") (class "Default")
      (node (ref "R23") (pin "1") (pinfunction "1_1") (pintype "passive"))
      (node (ref "U1") (pin "3") (pinfunction "GPIO_4_3") (pintype "bidirectional"))
    )
    (net (code "85") (name "Net-(U1-LRCK)") (class "Default")
      (node (ref "R16") (pin "1") (pinfunction "1_1") (pintype "passive"))
      (node (ref "U1") (pin "18") (pinfunction "LRCK_18") (pintype "bidirectional"))
    )
    (net (code "86") (name "Net-(U1-MCLK)") (class "Default")
      (node (ref "R14") (pin "1") (pinfunction "1_1") (pintype "passive"))
      (node (ref "U1") (pin "8") (pinfunction "MCLK_8") (pintype "bidirectional"))
    )
    (net (code "87") (name "Net-(U1-RSTN)") (class "Default")
      (node (ref "R11") (pin "2") (pinfunction "2_2") (pintype "passive"))
      (node (ref "U1") (pin "19") (pinfunction "RSTN_19") (pintype "bidirectional"))
    )
    (net (code "88") (name "Net-(U1-SDOUT1)") (class "Default")
      (node (ref "R17") (pin "1") (pinfunction "1_1") (pintype "passive"))
      (node (ref "U1") (pin "16") (pinfunction "SDOUT1_16") (pintype "bidirectional"))
    )
    (net (code "89") (name "Net-(U1-VDD_CORE)") (class "Default")
      (node (ref "C23") (pin "1") (pinfunction "1_1") (pintype "passive"))
      (node (ref "TP4") (pin "T") (pinfunction "T_T") (pintype "bidirectional"))
      (node (ref "U1") (pin "41") (pinfunction "VDD_CPOUT_41") (pintype "bidirectional"))
      (node (ref "U1") (pin "6") (pinfunction "VDD_CORE_6") (pintype "bidirectional"))
    )
    (net (code "90") (name "Net-(U1-VREF)") (class "Default")
      (node (ref "C11") (pin "2") (pinfunction "2_2") (pintype "passive"))
      (node (ref "TP3") (pin "T") (pinfunction "T_T") (pintype "bidirectional"))
      (node (ref "U1") (pin "30") (pinfunction "VREF_30") (pintype "bidirectional"))
    )
    (net (code "91") (name "Net-(U1-VRP)") (class "Default")
      (node (ref "C20") (pin "2") (pinfunction "2_2") (pintype "passive"))
      (node (ref "U1") (pin "31") (pinfunction "VRP_31") (pintype "bidirectional"))
    )
    (net (code "92") (name "SPI_MOSI") (class "Default")
      (node (ref "PI") (pin "19") (pinfunction "GPIO10/MOSI_19") (pintype "bidirectional"))
      (node (ref "R3") (pin "2") (pinfunction "2_2") (pintype "passive"))
    )
    (net (code "93") (name "SPI_SCLK") (class "Default")
      (node (ref "PI") (pin "23") (pinfunction "GPIO11/SCLK_23") (pintype "bidirectional"))
      (node (ref "R4") (pin "2") (pinfunction "2_2") (pintype "passive"))
    )
    (net (code "94") (name "VDD_3V3") (class "Default")
      (node (ref "C16") (pin "1") (pinfunction "1_1") (pintype "passive"))
      (node (ref "C19") (pin "1") (pinfunction "1_1") (pintype "passive"))
      (node (ref "C36") (pin "2") (pinfunction "2_2") (pintype "passive"))
      (node (ref "J1") (pin "3") (pinfunction "3_3") (pintype "bidirectional"))
      (node (ref "J2") (pin "3") (pinfunction "3_3") (pintype "bidirectional"))
      (node (ref "PI") (pin "17") (pinfunction "3V3_17") (pintype "power_in"))
      (node (ref "R11") (pin "1") (pinfunction "1_1") (pintype "passive"))
      (node (ref "R29") (pin "2") (pinfunction "2_2") (pintype "passive"))
      (node (ref "R30") (pin "2") (pinfunction "2_2") (pintype "passive"))
      (node (ref "U1") (pin "11") (pinfunction "VCC_I2S_11") (pintype "bidirectional"))
      (node (ref "U1") (pin "7") (pinfunction "VCC_DIO_7") (pintype "bidirectional"))
      (node (ref "X1") (pin "1") (pinfunction "ENABLE_1") (pintype "bidirectional"))
      (node (ref "X1") (pin "4") (pinfunction "VDD_4") (pintype "bidirectional"))
    )
    (net (code "95") (name "VDD_5V") (class "Default")
      (node (ref "C5") (pin "2") (pinfunction "2_2") (pintype "passive"))
      (node (ref "C6") (pin "2") (pinfunction "2_2") (pintype "passive"))
      (node (ref "PI") (pin "2") (pinfunction "5V0_2") (pintype "power_in"))
      (node (ref "PI") (pin "4") (pinfunction "5V0_4") (pintype "power_in"))
      (node (ref "R1") (pin "2") (pinfunction "2_2") (pintype "bidirectional"))
      (node (ref "R9") (pin "1") (pinfunction "1_1") (pintype "passive"))
      (node (ref "U1") (pin "27") (pinfunction "ALDOIN_27") (pintype "bidirectional"))
      (node (ref "U1") (pin "45") (pinfunction "DLDOIN_45") (pintype "bidirectional"))
    )
    (net (code "96") (name "unconnected-(D12-CKO-Pad2)") (class "Default")
      (node (ref "D12") (pin "2") (pinfunction "CKO_2") (pintype "bidirectional"))
    )
    (net (code "97") (name "unconnected-(D12-SDO-Pad3)") (class "Default")
      (node (ref "D12") (pin "3") (pinfunction "SDO_3") (pintype "bidirectional"))
    )
    (net (code "98") (name "unconnected-(PI-GEN4{slash}GPIO23-Pad16)") (class "Default")
      (node (ref "PI") (pin "16") (pinfunction "GEN4/GPIO23_16") (pintype "bidirectional"))
    )
    (net (code "99") (name "unconnected-(PI-GEN5{slash}GPIO24-Pad18)") (class "Default")
      (node (ref "PI") (pin "18") (pinfunction "GEN5/GPIO24_18") (pintype "bidirectional"))
    )
    (net (code "100") (name "unconnected-(PI-GEN6{slash}GPIO25-Pad22)") (class "Default")
      (node (ref "PI") (pin "22") (pinfunction "GEN6/GPIO25_22") (pintype "bidirectional"))
    )
    (net (code "101") (name "unconnected-(PI-GPIO4{slash}GCKL-Pad7)") (class "Default")
      (node (ref "PI") (pin "7") (pinfunction "GPIO4/GCKL_7") (pintype "bidirectional"))
    )
    (net (code "102") (name "unconnected-(PI-GPIO6-Pad31)") (class "Default")
      (node (ref "PI") (pin "31") (pinfunction "GPIO6_31") (pintype "bidirectional"))
    )
    (net (code "103") (name "unconnected-(PI-GPIO9{slash}MISO-Pad21)") (class "Default")
      (node (ref "PI") (pin "21") (pinfunction "GPIO9/MISO_21") (pintype "bidirectional"))
    )
    (net (code "104") (name "unconnected-(PI-GPIO16-Pad36)") (class "Default")
      (node (ref "PI") (pin "36") (pinfunction "GPIO16_36") (pintype "bidirectional"))
    )
    (net (code "105") (name "unconnected-(PI-GPIO22{slash}GEN3-Pad15)") (class "Default")
      (node (ref "PI") (pin "15") (pinfunction "GPIO22/GEN3_15") (pintype "bidirectional"))
    )
    (net (code "106") (name "unconnected-(PI-GPIO26-Pad37)") (class "Default")
      (node (ref "PI") (pin "37") (pinfunction "GPIO26_37") (pintype "bidirectional"))
    )
    (net (code "107") (name "unconnected-(PI-GPIO27{slash}GEN2-Pad13)") (class "Default")
      (node (ref "PI") (pin "13") (pinfunction "GPIO27/GEN2_13") (pintype "bidirectional"))
    )
    (net (code "108") (name "unconnected-(PI-ID_SC-Pad28)") (class "Default")
      (node (ref "PI") (pin "28") (pinfunction "ID_SC_28") (pintype "bidirectional"))
    )
    (net (code "109") (name "unconnected-(PI-ID_SD-Pad27)") (class "Default")
      (node (ref "PI") (pin "27") (pinfunction "ID_SD_27") (pintype "bidirectional"))
    )
    (net (code "110") (name "unconnected-(PI-RXD0{slash}GPIO15-Pad10)") (class "Default")
      (node (ref "PI") (pin "10") (pinfunction "RXD0/GPIO15_10") (pintype "bidirectional"))
    )
    (net (code "111") (name "unconnected-(PI-TXD0{slash}GPIO14-Pad8)") (class "Default")
      (node (ref "PI") (pin "8") (pinfunction "TXD0/GPIO14_8") (pintype "bidirectional"))
    )
    (net (code "112") (name "unconnected-(PI-~{CE0}{slash}GPIO8-Pad24)") (class "Default")
      (node (ref "PI") (pin "24") (pinfunction "~{CE0}/GPIO8_24") (pintype "bidirectional"))
    )
    (net (code "113") (name "unconnected-(PI-~{CE}{slash}GPIO7-Pad26)") (class "Default")
      (node (ref "PI") (pin "26") (pinfunction "~{CE}/GPIO7_26") (pintype "bidirectional"))
    )
    (net (code "114") (name "unconnected-(U1-MICBIAS1-Pad21)") (class "Default")
      (node (ref "U1") (pin "21") (pinfunction "MICBIAS1_21") (pintype "bidirectional"))
    )
    (net (code "115") (name "unconnected-(U1-MICBIAS2-Pad24)") (class "Default")
      (node (ref "U1") (pin "24") (pinfunction "MICBIAS2_24") (pintype "bidirectional"))
    )
    (net (code "116") (name "unconnected-(U1-MICBIAS3-Pad34)") (class "Default")
      (node (ref "U1") (pin "34") (pinfunction "MICBIAS3_34") (pintype "bidirectional"))
    )
    (net (code "117") (name "unconnected-(U1-MICBIAS4-Pad37)") (class "Default")
      (node (ref "U1") (pin "37") (pinfunction "MICBIAS4_37") (pintype "bidirectional"))
    )
    (net (code "118") (name "unconnected-(U1-NC1-Pad12)") (class "Default")
      (node (ref "U1") (pin "12") (pinfunction "NC1_12") (pintype "bidirectional"))
    )
    (net (code "119") (name "unconnected-(U1-NC2-Pad13)") (class "Default")
      (node (ref "U1") (pin "13") (pinfunction "NC2_13") (pintype "bidirectional"))
    )
    (net (code "120") (name "unconnected-(U1-NC3-Pad14)") (class "Default")
      (node (ref "U1") (pin "14") (pinfunction "NC3_14") (pintype "bidirectional"))
    )
    (net (code "121") (name "unconnected-(U1-NC4-Pad47)") (class "Default")
      (node (ref "U1") (pin "47") (pinfunction "NC4_47") (pintype "bidirectional"))
    )
    (net (code "122") (name "unconnected-(U1-SDOUT2-Pad17)") (class "Default")
      (node (ref "U1") (pin "17") (pinfunction "SDOUT2_17") (pintype "bidirectional"))
    )
  )
)
